# power.net
KiCad netlist of a schematic drawn in Altium Designer
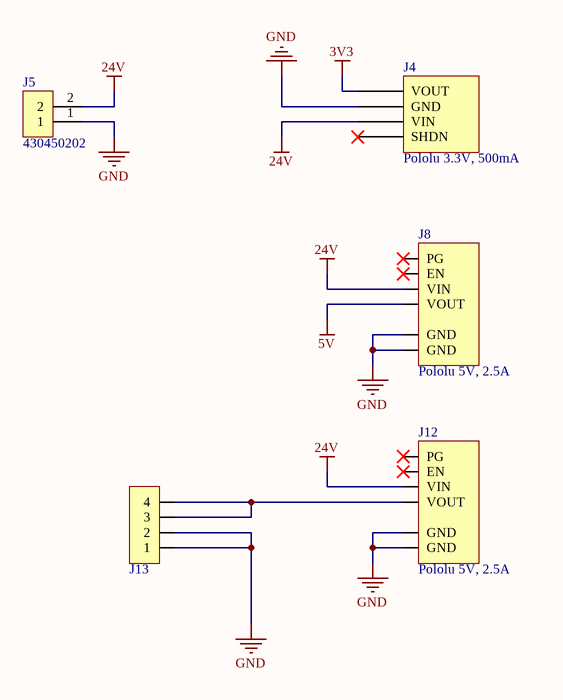
[diagram p0: power.SchDoc]

(export (version "E")
  (design (tool "Eeschema 10.0.6"))
  (components
    (comp (ref "J4")
      (value "Pololu 3.3V, 500mA")
      (footprint "Pololu 3.3V, 500mA Step-Down Voltage Regulator D24V5F3 - duplicate")
      (libsource (lib "brew_lib") (part "Pololu 3.3V, 500mA Step-Down Voltage Regulator D24V5F3"))
    )
    (comp (ref "J5")
      (value "__Template_Connector_1X2")
      (footprint "MOLEX_430450202")
      (description "CONN, HDR, R/A, 2x1, 3MM P, 7.37MM H, GOLD, TH")
      (fields (field (name "MFG") "Molex, LLC") (field (name "MFG P/N") "430450202"))
      (libsource (lib "AltiumReleaseLibDB") (part "__Template_Connector_1X2"))
    )
    (comp (ref "J8")
      (value "Pololu 5V, 2.5A")
      (footprint "Pololu 5V, 2.5A Step-Down Voltage Regulator D24V22F5")
      (libsource (lib "brew_lib") (part "Pololu 5V, 2.5A Step-Down Voltage Regulator D24V22F5"))
    )
    (comp (ref "J12")
      (value "Pololu 5V, 2.5A")
      (footprint "Pololu 5V, 2.5A Step-Down Voltage Regulator D24V22F5")
      (libsource (lib "brew_lib") (part "Pololu 5V, 2.5A Step-Down Voltage Regulator D24V22F5"))
    )
    (comp (ref "J13") (value "1x4_PIN") (footprint "1x4_PIN") (libsource (lib "brew_lib") (part "1x4_PIN")))
  )
  (nets
    (net (code "1") (name "3V3") (class "Default")
      (node (ref "J4") (pin "1") (pinfunction "VOUT_1") (pintype "passive"))
    )
    (net (code "2") (name "5V") (class "Default")
      (node (ref "J8") (pin "5") (pinfunction "VOUT_5") (pintype "passive"))
    )
    (net (code "3") (name "24V") (class "Default")
      (node (ref "J12") (pin "3") (pinfunction "VIN_3") (pintype "passive"))
      (node (ref "J4") (pin "3") (pinfunction "VIN_3") (pintype "passive"))
      (node (ref "J5") (pin "2") (pinfunction "2_2") (pintype "passive"))
      (node (ref "J8") (pin "3") (pinfunction "VIN_3") (pintype "passive"))
    )
    (net (code "4") (name "GND") (class "Default")
      (node (ref "J12") (pin "4") (pinfunction "GND_4") (pintype "passive"))
      (node (ref "J12") (pin "6") (pinfunction "GND_6") (pintype "passive"))
      (node (ref "J13") (pin "1") (pinfunction "1_1") (pintype "passive"))
      (node (ref "J13") (pin "2") (pinfunction "2_2") (pintype "passive"))
      (node (ref "J4") (pin "2") (pinfunction "GND_2") (pintype "passive"))
      (node (ref "J5") (pin "1") (pinfunction "1_1") (pintype "passive"))
      (node (ref "J8") (pin "4") (pinfunction "GND_4") (pintype "passive"))
      (node (ref "J8") (pin "6") (pinfunction "GND_6") (pintype "passive"))
    )
    (net (code "5") (name "Net-(J12-VOUT)") (class "Default")
      (node (ref "J12") (pin "5") (pinfunction "VOUT_5") (pintype "passive"))
      (node (ref "J13") (pin "3") (pinfunction "3_3") (pintype "passive"))
      (node (ref "J13") (pin "4") (pinfunction "4_4") (pintype "passive"))
    )
    (net (code "6") (name "unconnected-(J4-SHDN-Pad4)") (class "Default")
      (node (ref "J4") (pin "4") (pinfunction "SHDN_4") (pintype "passive+no_connect"))
    )
    (net (code "7") (name "unconnected-(J8-EN-Pad2)") (class "Default")
      (node (ref "J8") (pin "2") (pinfunction "EN_2") (pintype "passive+no_connect"))
    )
    (net (code "8") (name "unconnected-(J8-PG-Pad1)") (class "Default")
      (node (ref "J8") (pin "1") (pinfunction "PG_1") (pintype "passive+no_connect"))
    )
    (net (code "9") (name "unconnected-(J12-EN-Pad2)") (class "Default")
      (node (ref "J12") (pin "2") (pinfunction "EN_2") (pintype "passive+no_connect"))
    )
    (net (code "10") (name "unconnected-(J12-PG-Pad1)") (class "Default")
      (node (ref "J12") (pin "1") (pinfunction "PG_1") (pintype "passive+no_connect"))
    )
  )
)
